# core09e2.net
KiCad netlist of a schematic drawn in EAGLE
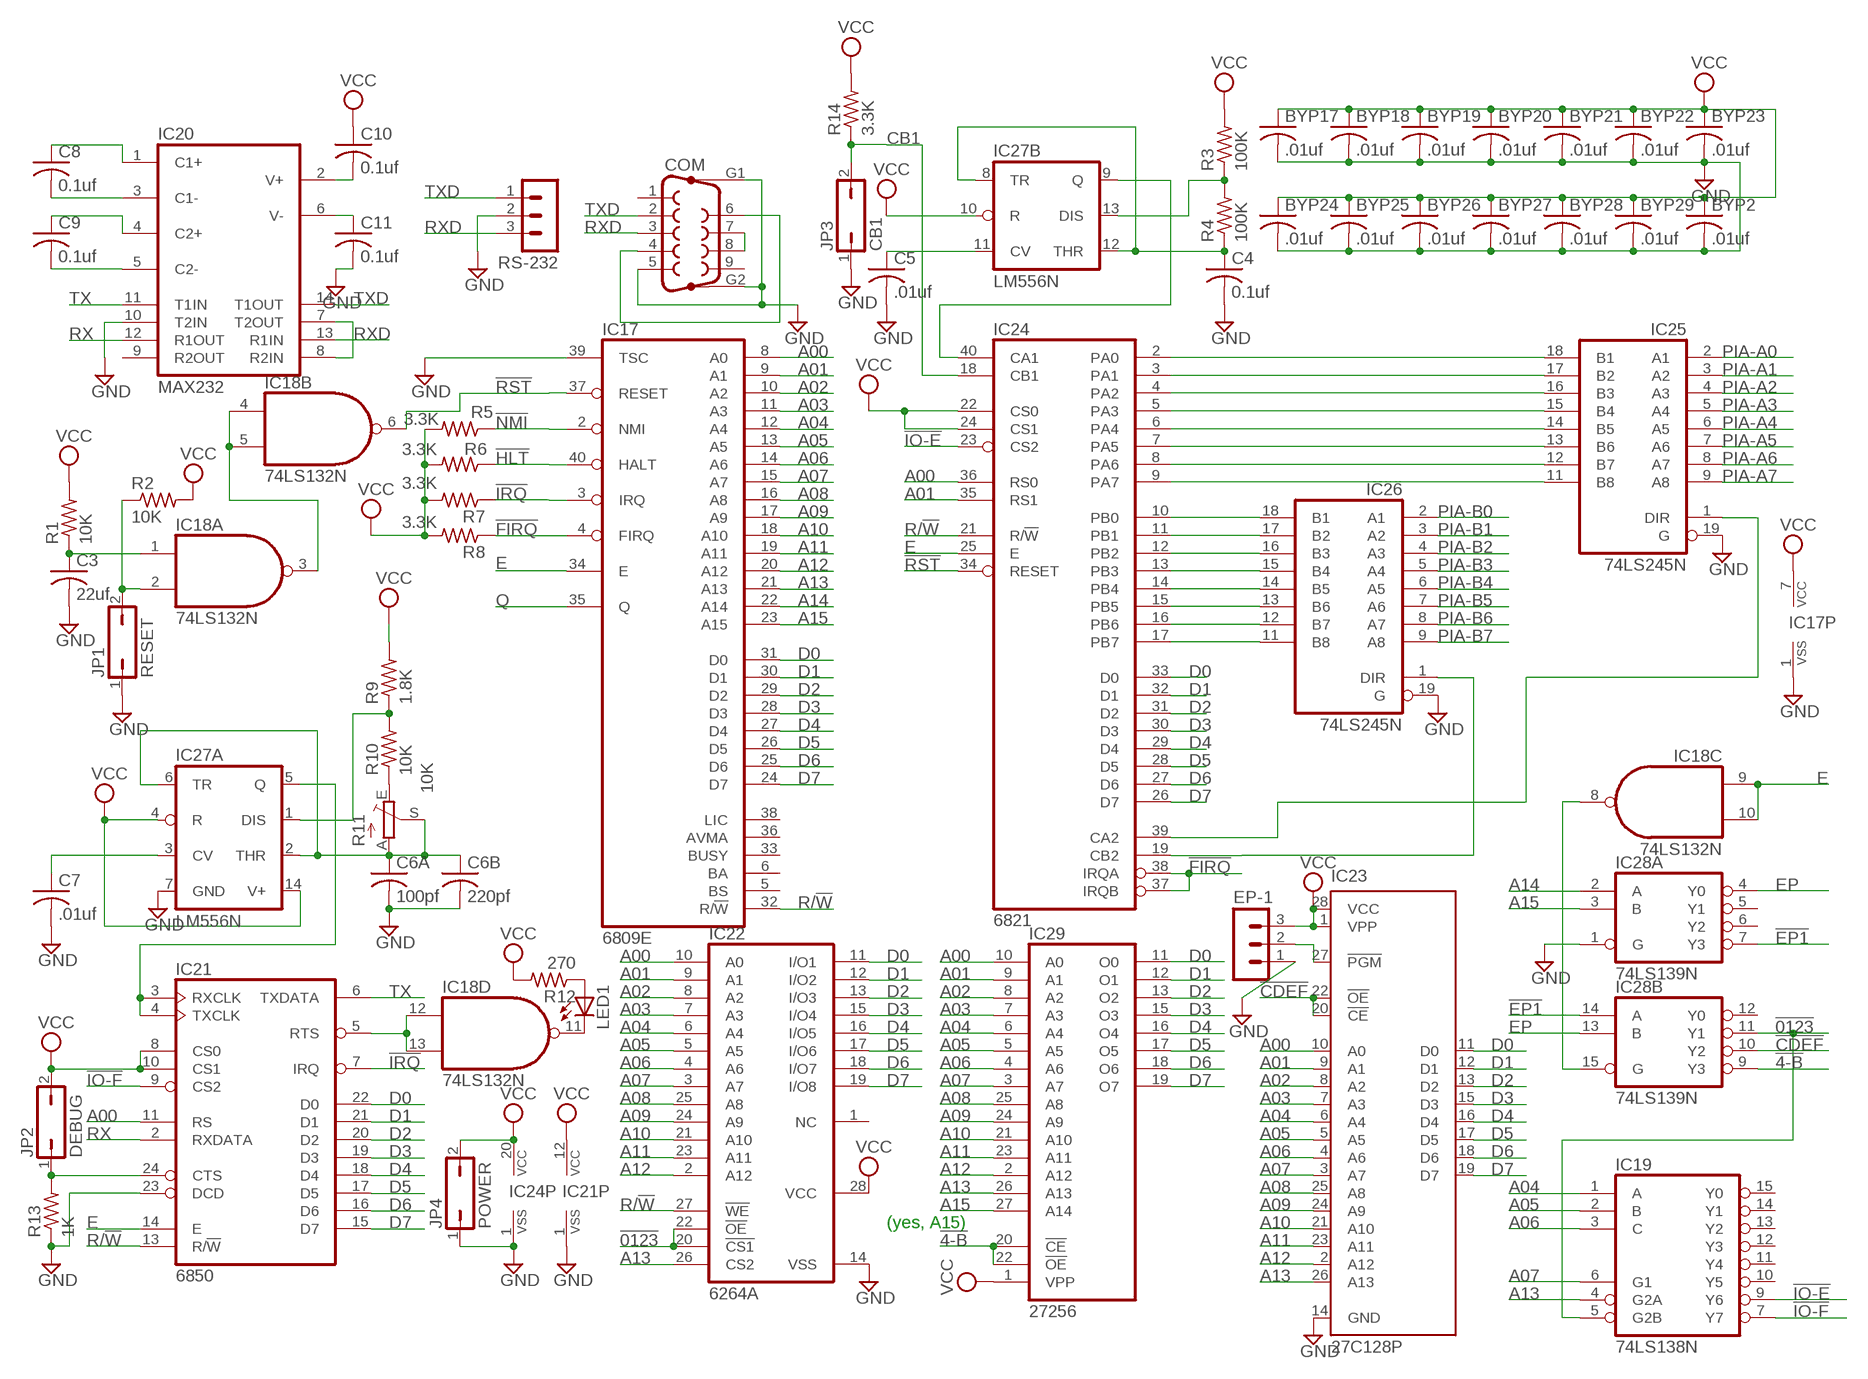
[diagram p0: schematic, sheet 1]
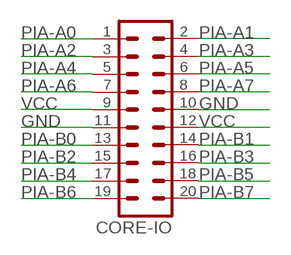
[diagram p1: schematic, sheet 2]
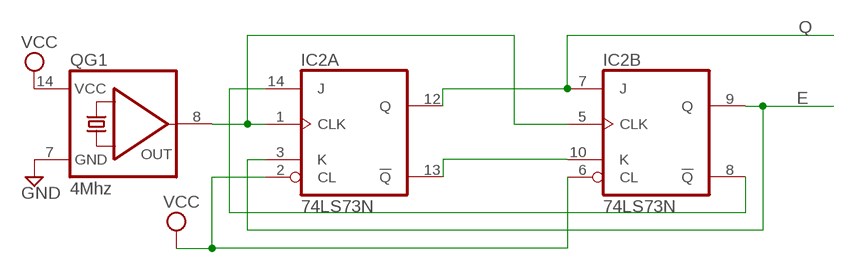
[diagram p2: schematic, sheet 3]

(export (version "E")
  (design (tool "Eeschema 10.0.6"))
  (components
    (comp (ref "BYP2")
      (value ".01uf")
      (footprint "eagle-import:C050-025X075")
      (libsource (lib "eagle-import") (part "C-US050-025X075"))
    )
    (comp (ref "BYP17")
      (value ".01uf")
      (footprint "eagle-import:C050-025X075")
      (libsource (lib "eagle-import") (part "C-US050-025X075"))
    )
    (comp (ref "BYP18")
      (value ".01uf")
      (footprint "eagle-import:C050-025X075")
      (libsource (lib "eagle-import") (part "C-US050-025X075"))
    )
    (comp (ref "BYP19")
      (value ".01uf")
      (footprint "eagle-import:C050-025X075")
      (libsource (lib "eagle-import") (part "C-US050-025X075"))
    )
    (comp (ref "BYP20")
      (value ".01uf")
      (footprint "eagle-import:C050-025X075")
      (libsource (lib "eagle-import") (part "C-US050-025X075"))
    )
    (comp (ref "BYP21")
      (value ".01uf")
      (footprint "eagle-import:C050-025X075")
      (libsource (lib "eagle-import") (part "C-US050-025X075"))
    )
    (comp (ref "BYP22")
      (value ".01uf")
      (footprint "eagle-import:C050-025X075")
      (libsource (lib "eagle-import") (part "C-US050-025X075"))
    )
    (comp (ref "BYP23")
      (value ".01uf")
      (footprint "eagle-import:C050-025X075")
      (libsource (lib "eagle-import") (part "C-US050-025X075"))
    )
    (comp (ref "BYP24")
      (value ".01uf")
      (footprint "eagle-import:C050-025X075")
      (libsource (lib "eagle-import") (part "C-US050-025X075"))
    )
    (comp (ref "BYP25")
      (value ".01uf")
      (footprint "eagle-import:C050-025X075")
      (libsource (lib "eagle-import") (part "C-US050-025X075"))
    )
    (comp (ref "BYP26")
      (value ".01uf")
      (footprint "eagle-import:C050-025X075")
      (libsource (lib "eagle-import") (part "C-US050-025X075"))
    )
    (comp (ref "BYP27")
      (value ".01uf")
      (footprint "eagle-import:C050-025X075")
      (libsource (lib "eagle-import") (part "C-US050-025X075"))
    )
    (comp (ref "BYP28")
      (value ".01uf")
      (footprint "eagle-import:C050-025X075")
      (libsource (lib "eagle-import") (part "C-US050-025X075"))
    )
    (comp (ref "BYP29")
      (value ".01uf")
      (footprint "eagle-import:C050-025X075")
      (libsource (lib "eagle-import") (part "C-US050-025X075"))
    )
    (comp (ref "C3")
      (value "22uf")
      (footprint "eagle-import:C102-054X133")
      (libsource (lib "eagle-import") (part "C-US102-054X133"))
    )
    (comp (ref "C4")
      (value "0.1uf")
      (footprint "eagle-import:C050-025X075")
      (libsource (lib "eagle-import") (part "C-US050-025X075"))
    )
    (comp (ref "C5")
      (value ".01uf")
      (footprint "eagle-import:C050-025X075")
      (libsource (lib "eagle-import") (part "C-US050-025X075"))
    )
    (comp (ref "C6A")
      (value "100pf")
      (footprint "eagle-import:C050-025X075")
      (libsource (lib "eagle-import") (part "C-US050-025X075"))
    )
    (comp (ref "C6B")
      (value "220pf")
      (footprint "eagle-import:C050-025X075")
      (libsource (lib "eagle-import") (part "C-US050-025X075"))
    )
    (comp (ref "C7")
      (value ".01uf")
      (footprint "eagle-import:C050-025X075")
      (libsource (lib "eagle-import") (part "C-US050-025X075"))
    )
    (comp (ref "C8")
      (value "0.1uf")
      (footprint "eagle-import:C050-025X075")
      (libsource (lib "eagle-import") (part "C-US050-025X075"))
    )
    (comp (ref "C9")
      (value "0.1uf")
      (footprint "eagle-import:C050-025X075")
      (libsource (lib "eagle-import") (part "C-US050-025X075"))
    )
    (comp (ref "C10")
      (value "0.1uf")
      (footprint "eagle-import:C050-025X075")
      (libsource (lib "eagle-import") (part "C-US050-025X075"))
    )
    (comp (ref "C11")
      (value "0.1uf")
      (footprint "eagle-import:C050-025X075")
      (libsource (lib "eagle-import") (part "C-US050-025X075"))
    )
    (comp (ref "COM")
      (value "F09HP")
      (footprint "eagle-import:F09HP")
      (libsource (lib "eagle-import") (part "F09HP"))
    )
    (comp (ref "EP-1")
      (value "MA03-1")
      (footprint "eagle-import:MA03-1")
      (libsource (lib "eagle-import") (part "MA03-1"))
    )
    (comp (ref "IC17")
      (value "6809E")
      (footprint "eagle-import:DIL40")
      (fields (field (name "MF") "NTE ELECTRONICS") (field (name "MPN") "NTE6809E"))
      (libsource (lib "eagle-import") (part "6809E"))
    )
    (comp (ref "IC18")
      (value "74LS132N")
      (footprint "eagle-import:DIL14")
      (libsource (lib "eagle-import") (part "7400NLS"))
    )
    (comp (ref "IC19")
      (value "74LS138N")
      (footprint "eagle-import:DIL16")
      (libsource (lib "eagle-import") (part "74138NLS"))
    )
    (comp (ref "IC20")
      (value "MAX232")
      (footprint "eagle-import:DIL16")
      (fields (field (name "MF") "MAXIM") (field (name "MPN") "MAX232ACPE+"))
      (libsource (lib "eagle-import") (part "MAX232"))
    )
    (comp (ref "IC21")
      (value "6850")
      (footprint "eagle-import:DIL24")
      (fields (field (name "MF") "NTE ELECTRONICS") (field (name "MPN") "NTE6850"))
      (libsource (lib "eagle-import") (part "6850"))
    )
    (comp (ref "IC22")
      (value "6264A")
      (footprint "eagle-import:DIL28-6")
      (libsource (lib "eagle-import") (part "6264A"))
    )
    (comp (ref "IC23")
      (value "27C128P")
      (footprint "eagle-import:DIL28-6")
      (libsource (lib "eagle-import") (part "27128PC"))
    )
    (comp (ref "IC24")
      (value "6821")
      (footprint "eagle-import:DIL40")
      (fields (field (name "MF") "NTE ELECTRONICS") (field (name "MPN") "NTE6821"))
      (libsource (lib "eagle-import") (part "6821"))
    )
    (comp (ref "IC25")
      (value "74LS245N")
      (footprint "eagle-import:DIL20")
      (libsource (lib "eagle-import") (part "74245NLS"))
    )
    (comp (ref "IC26")
      (value "74LS245N")
      (footprint "eagle-import:DIL20")
      (libsource (lib "eagle-import") (part "74245NLS"))
    )
    (comp (ref "IC27")
      (value "LM556N")
      (footprint "eagle-import:DIL14")
      (libsource (lib "eagle-import") (part "556NLM"))
    )
    (comp (ref "IC28")
      (value "74LS139N")
      (footprint "eagle-import:DIL16")
      (libsource (lib "eagle-import") (part "74139NLS"))
    )
    (comp (ref "IC29")
      (value "27256")
      (footprint "eagle-import:DIL28")
      (libsource (lib "eagle-import") (part "27256"))
    )
    (comp (ref "JP1")
      (value "RESET")
      (footprint "eagle-import:JP1")
      (libsource (lib "eagle-import") (part "JP1Q"))
    )
    (comp (ref "JP2")
      (value "DEBUG")
      (footprint "eagle-import:JP1")
      (libsource (lib "eagle-import") (part "JP1Q"))
    )
    (comp (ref "JP3")
      (value "CB1")
      (footprint "eagle-import:JP1")
      (libsource (lib "eagle-import") (part "JP1Q"))
    )
    (comp (ref "JP4")
      (value "POWER")
      (footprint "eagle-import:JP1")
      (libsource (lib "eagle-import") (part "JP1Q"))
    )
    (comp (ref "LED1")
      (value "LED3MM")
      (footprint "eagle-import:LED3MM")
      (libsource (lib "eagle-import") (part "LED3MM"))
    )
    (comp (ref "R1")
      (value "10K")
      (footprint "eagle-import:0207_7")
      (libsource (lib "eagle-import") (part "R-US_0207/7"))
    )
    (comp (ref "R2")
      (value "10K")
      (footprint "eagle-import:0207_7")
      (libsource (lib "eagle-import") (part "R-US_0207/7"))
    )
    (comp (ref "R3")
      (value "100K")
      (footprint "eagle-import:0207_7")
      (libsource (lib "eagle-import") (part "R-US_0207/7"))
    )
    (comp (ref "R4")
      (value "100K")
      (footprint "eagle-import:0207_7")
      (libsource (lib "eagle-import") (part "R-US_0207/7"))
    )
    (comp (ref "R5")
      (value "3.3K")
      (footprint "eagle-import:0207_7")
      (libsource (lib "eagle-import") (part "R-US_0207/7"))
    )
    (comp (ref "R6")
      (value "3.3K")
      (footprint "eagle-import:0207_7")
      (libsource (lib "eagle-import") (part "R-US_0207/7"))
    )
    (comp (ref "R7")
      (value "3.3K")
      (footprint "eagle-import:0207_7")
      (libsource (lib "eagle-import") (part "R-US_0207/7"))
    )
    (comp (ref "R8")
      (value "3.3K")
      (footprint "eagle-import:0207_7")
      (libsource (lib "eagle-import") (part "R-US_0207/7"))
    )
    (comp (ref "R9")
      (value "1.8K")
      (footprint "eagle-import:0207_7")
      (libsource (lib "eagle-import") (part "R-US_0207/7"))
    )
    (comp (ref "R10")
      (value "10K")
      (footprint "eagle-import:0207_7")
      (libsource (lib "eagle-import") (part "R-US_0207/7"))
    )
    (comp (ref "R11")
      (value "10K")
      (footprint "eagle-import:SP19L")
      (libsource (lib "eagle-import") (part "TRIM_EU-B90P"))
    )
    (comp (ref "R12")
      (value "270")
      (footprint "eagle-import:0207_7")
      (libsource (lib "eagle-import") (part "R-US_0207/7"))
    )
    (comp (ref "R13")
      (value "1K")
      (footprint "eagle-import:0207_7")
      (libsource (lib "eagle-import") (part "R-US_0207/7"))
    )
    (comp (ref "R14")
      (value "3.3K")
      (footprint "eagle-import:0207_7")
      (libsource (lib "eagle-import") (part "R-US_0207/7"))
    )
    (comp (ref "RS-232")
      (value "MA03-1")
      (footprint "eagle-import:MA03-1")
      (libsource (lib "eagle-import") (part "MA03-1"))
    )
    (comp (ref "IC2")
      (value "74LS73N")
      (footprint "eagle-import:DIL14")
      (libsource (lib "eagle-import") (part "7473NLS"))
    )
    (comp (ref "QG1")
      (value "4Mhz")
      (footprint "eagle-import:DIL14S")
      (libsource (lib "eagle-import") (part "QG5860"))
    )
    (comp (ref "CORE-IO")
      (value "MA10-2")
      (footprint "eagle-import:MA10-2")
      (libsource (lib "eagle-import") (part "MA10-2"))
    )
  )
  (nets
    (net (code "1") (name "A00") (class "Default")
      (node (ref "IC17") (pin "8") (pinfunction "A0_8") (pintype "tri_state"))
      (node (ref "IC21") (pin "11") (pinfunction "RS_11") (pintype "input"))
      (node (ref "IC22") (pin "10") (pinfunction "A0_10") (pintype "input"))
      (node (ref "IC23") (pin "10") (pinfunction "A0_10") (pintype "input"))
      (node (ref "IC24") (pin "36") (pinfunction "RS0_36") (pintype "input"))
      (node (ref "IC29") (pin "10") (pinfunction "A0_10") (pintype "input"))
    )
    (net (code "2") (name "A01") (class "Default")
      (node (ref "IC17") (pin "9") (pinfunction "A1_9") (pintype "tri_state"))
      (node (ref "IC22") (pin "9") (pinfunction "A1_9") (pintype "input"))
      (node (ref "IC23") (pin "9") (pinfunction "A1_9") (pintype "input"))
      (node (ref "IC24") (pin "35") (pinfunction "RS1_35") (pintype "input"))
      (node (ref "IC29") (pin "9") (pinfunction "A1_9") (pintype "input"))
    )
    (net (code "3") (name "A02") (class "Default")
      (node (ref "IC17") (pin "10") (pinfunction "A2_10") (pintype "tri_state"))
      (node (ref "IC22") (pin "8") (pinfunction "A2_8") (pintype "input"))
      (node (ref "IC23") (pin "8") (pinfunction "A2_8") (pintype "input"))
      (node (ref "IC29") (pin "8") (pinfunction "A2_8") (pintype "input"))
    )
    (net (code "4") (name "A03") (class "Default")
      (node (ref "IC17") (pin "11") (pinfunction "A3_11") (pintype "tri_state"))
      (node (ref "IC22") (pin "7") (pinfunction "A3_7") (pintype "input"))
      (node (ref "IC23") (pin "7") (pinfunction "A3_7") (pintype "input"))
      (node (ref "IC29") (pin "7") (pinfunction "A3_7") (pintype "input"))
    )
    (net (code "5") (name "A04") (class "Default")
      (node (ref "IC17") (pin "12") (pinfunction "A4_12") (pintype "tri_state"))
      (node (ref "IC19") (pin "1") (pinfunction "A_1") (pintype "input"))
      (node (ref "IC22") (pin "6") (pinfunction "A4_6") (pintype "input"))
      (node (ref "IC23") (pin "6") (pinfunction "A4_6") (pintype "input"))
      (node (ref "IC29") (pin "6") (pinfunction "A4_6") (pintype "input"))
    )
    (net (code "6") (name "A05") (class "Default")
      (node (ref "IC17") (pin "13") (pinfunction "A5_13") (pintype "tri_state"))
      (node (ref "IC19") (pin "2") (pinfunction "B_2") (pintype "input"))
      (node (ref "IC22") (pin "5") (pinfunction "A5_5") (pintype "input"))
      (node (ref "IC23") (pin "5") (pinfunction "A5_5") (pintype "input"))
      (node (ref "IC29") (pin "5") (pinfunction "A5_5") (pintype "input"))
    )
    (net (code "7") (name "A06") (class "Default")
      (node (ref "IC17") (pin "14") (pinfunction "A6_14") (pintype "tri_state"))
      (node (ref "IC19") (pin "3") (pinfunction "C_3") (pintype "input"))
      (node (ref "IC22") (pin "4") (pinfunction "A6_4") (pintype "input"))
      (node (ref "IC23") (pin "4") (pinfunction "A6_4") (pintype "input"))
      (node (ref "IC29") (pin "4") (pinfunction "A6_4") (pintype "input"))
    )
    (net (code "8") (name "A07") (class "Default")
      (node (ref "IC17") (pin "15") (pinfunction "A7_15") (pintype "tri_state"))
      (node (ref "IC19") (pin "6") (pinfunction "G1_6") (pintype "input"))
      (node (ref "IC22") (pin "3") (pinfunction "A7_3") (pintype "input"))
      (node (ref "IC23") (pin "3") (pinfunction "A7_3") (pintype "input"))
      (node (ref "IC29") (pin "3") (pinfunction "A7_3") (pintype "input"))
    )
    (net (code "9") (name "A08") (class "Default")
      (node (ref "IC17") (pin "16") (pinfunction "A8_16") (pintype "tri_state"))
      (node (ref "IC22") (pin "25") (pinfunction "A8_25") (pintype "input"))
      (node (ref "IC23") (pin "25") (pinfunction "A8_25") (pintype "input"))
      (node (ref "IC29") (pin "25") (pinfunction "A8_25") (pintype "input"))
    )
    (net (code "10") (name "A09") (class "Default")
      (node (ref "IC17") (pin "17") (pinfunction "A9_17") (pintype "tri_state"))
      (node (ref "IC22") (pin "24") (pinfunction "A9_24") (pintype "input"))
      (node (ref "IC23") (pin "24") (pinfunction "A9_24") (pintype "input"))
      (node (ref "IC29") (pin "24") (pinfunction "A9_24") (pintype "input"))
    )
    (net (code "11") (name "A10") (class "Default")
      (node (ref "IC17") (pin "18") (pinfunction "A10_18") (pintype "tri_state"))
      (node (ref "IC22") (pin "21") (pinfunction "A10_21") (pintype "input"))
      (node (ref "IC23") (pin "21") (pinfunction "A10_21") (pintype "input"))
      (node (ref "IC29") (pin "21") (pinfunction "A10_21") (pintype "input"))
    )
    (net (code "12") (name "A11") (class "Default")
      (node (ref "IC17") (pin "19") (pinfunction "A11_19") (pintype "tri_state"))
      (node (ref "IC22") (pin "23") (pinfunction "A11_23") (pintype "input"))
      (node (ref "IC23") (pin "23") (pinfunction "A11_23") (pintype "input"))
      (node (ref "IC29") (pin "23") (pinfunction "A11_23") (pintype "input"))
    )
    (net (code "13") (name "A12") (class "Default")
      (node (ref "IC17") (pin "20") (pinfunction "A12_20") (pintype "tri_state"))
      (node (ref "IC22") (pin "2") (pinfunction "A12_2") (pintype "input"))
      (node (ref "IC23") (pin "2") (pinfunction "A12_2") (pintype "input"))
      (node (ref "IC29") (pin "2") (pinfunction "A12_2") (pintype "input"))
    )
    (net (code "14") (name "A13") (class "Default")
      (node (ref "IC17") (pin "21") (pinfunction "A13_21") (pintype "tri_state"))
      (node (ref "IC19") (pin "4") (pinfunction "G2A_4") (pintype "input"))
      (node (ref "IC22") (pin "26") (pinfunction "CS2_26") (pintype "input"))
      (node (ref "IC23") (pin "26") (pinfunction "A13_26") (pintype "input"))
      (node (ref "IC29") (pin "26") (pinfunction "A13_26") (pintype "input"))
    )
    (net (code "15") (name "A14") (class "Default")
      (node (ref "IC17") (pin "22") (pinfunction "A14_22") (pintype "tri_state"))
      (node (ref "IC28") (pin "2") (pinfunction "A_2") (pintype "input"))
    )
    (net (code "16") (name "A15") (class "Default")
      (node (ref "IC17") (pin "23") (pinfunction "A15_23") (pintype "tri_state"))
      (node (ref "IC28") (pin "3") (pinfunction "B_3") (pintype "input"))
      (node (ref "IC29") (pin "27") (pinfunction "A14_27") (pintype "input"))
    )
    (net (code "17") (name "CB1") (class "Default")
      (node (ref "IC24") (pin "18") (pinfunction "CB1_18") (pintype "input"))
      (node (ref "JP3") (pin "2") (pinfunction "2_2") (pintype "passive"))
      (node (ref "R14") (pin "1") (pinfunction "1_1") (pintype "passive"))
    )
    (net (code "18") (name "D0") (class "Default")
      (node (ref "IC17") (pin "31") (pinfunction "D0_31") (pintype "bidirectional"))
      (node (ref "IC21") (pin "22") (pinfunction "D0_22") (pintype "bidirectional"))
      (node (ref "IC22") (pin "11") (pinfunction "I/O1_11") (pintype "bidirectional"))
      (node (ref "IC23") (pin "11") (pinfunction "D0_11") (pintype "tri_state"))
      (node (ref "IC24") (pin "33") (pinfunction "D0_33") (pintype "bidirectional"))
      (node (ref "IC29") (pin "11") (pinfunction "O0_11") (pintype "tri_state"))
    )
    (net (code "19") (name "D1") (class "Default")
      (node (ref "IC17") (pin "30") (pinfunction "D1_30") (pintype "bidirectional"))
      (node (ref "IC21") (pin "21") (pinfunction "D1_21") (pintype "bidirectional"))
      (node (ref "IC22") (pin "12") (pinfunction "I/O2_12") (pintype "bidirectional"))
      (node (ref "IC23") (pin "12") (pinfunction "D1_12") (pintype "tri_state"))
      (node (ref "IC24") (pin "32") (pinfunction "D1_32") (pintype "bidirectional"))
      (node (ref "IC29") (pin "12") (pinfunction "O1_12") (pintype "tri_state"))
    )
    (net (code "20") (name "D2") (class "Default")
      (node (ref "IC17") (pin "29") (pinfunction "D2_29") (pintype "bidirectional"))
      (node (ref "IC21") (pin "20") (pinfunction "D2_20") (pintype "bidirectional"))
      (node (ref "IC22") (pin "13") (pinfunction "I/O3_13") (pintype "bidirectional"))
      (node (ref "IC23") (pin "13") (pinfunction "D2_13") (pintype "tri_state"))
      (node (ref "IC24") (pin "31") (pinfunction "D2_31") (pintype "bidirectional"))
      (node (ref "IC29") (pin "13") (pinfunction "O2_13") (pintype "tri_state"))
    )
    (net (code "21") (name "D3") (class "Default")
      (node (ref "IC17") (pin "28") (pinfunction "D3_28") (pintype "bidirectional"))
      (node (ref "IC21") (pin "19") (pinfunction "D3_19") (pintype "bidirectional"))
      (node (ref "IC22") (pin "15") (pinfunction "I/O4_15") (pintype "bidirectional"))
      (node (ref "IC23") (pin "15") (pinfunction "D3_15") (pintype "tri_state"))
      (node (ref "IC24") (pin "30") (pinfunction "D3_30") (pintype "bidirectional"))
      (node (ref "IC29") (pin "15") (pinfunction "O3_15") (pintype "tri_state"))
    )
    (net (code "22") (name "D4") (class "Default")
      (node (ref "IC17") (pin "27") (pinfunction "D4_27") (pintype "bidirectional"))
      (node (ref "IC21") (pin "18") (pinfunction "D4_18") (pintype "bidirectional"))
      (node (ref "IC22") (pin "16") (pinfunction "I/O5_16") (pintype "bidirectional"))
      (node (ref "IC23") (pin "16") (pinfunction "D4_16") (pintype "tri_state"))
      (node (ref "IC24") (pin "29") (pinfunction "D4_29") (pintype "bidirectional"))
      (node (ref "IC29") (pin "16") (pinfunction "O4_16") (pintype "tri_state"))
    )
    (net (code "23") (name "D5") (class "Default")
      (node (ref "IC17") (pin "26") (pinfunction "D5_26") (pintype "bidirectional"))
      (node (ref "IC21") (pin "17") (pinfunction "D5_17") (pintype "bidirectional"))
      (node (ref "IC22") (pin "17") (pinfunction "I/O6_17") (pintype "bidirectional"))
      (node (ref "IC23") (pin "17") (pinfunction "D5_17") (pintype "tri_state"))
      (node (ref "IC24") (pin "28") (pinfunction "D5_28") (pintype "bidirectional"))
      (node (ref "IC29") (pin "17") (pinfunction "O5_17") (pintype "tri_state"))
    )
    (net (code "24") (name "D6") (class "Default")
      (node (ref "IC17") (pin "25") (pinfunction "D6_25") (pintype "bidirectional"))
      (node (ref "IC21") (pin "16") (pinfunction "D6_16") (pintype "bidirectional"))
      (node (ref "IC22") (pin "18") (pinfunction "I/O7_18") (pintype "bidirectional"))
      (node (ref "IC23") (pin "18") (pinfunction "D6_18") (pintype "tri_state"))
      (node (ref "IC24") (pin "27") (pinfunction "D6_27") (pintype "bidirectional"))
      (node (ref "IC29") (pin "18") (pinfunction "O6_18") (pintype "tri_state"))
    )
    (net (code "25") (name "D7") (class "Default")
      (node (ref "IC17") (pin "24") (pinfunction "D7_24") (pintype "bidirectional"))
      (node (ref "IC21") (pin "15") (pinfunction "D7_15") (pintype "bidirectional"))
      (node (ref "IC22") (pin "19") (pinfunction "I/O8_19") (pintype "bidirectional"))
      (node (ref "IC23") (pin "19") (pinfunction "D7_19") (pintype "tri_state"))
      (node (ref "IC24") (pin "26") (pinfunction "D7_26") (pintype "bidirectional"))
      (node (ref "IC29") (pin "19") (pinfunction "O7_19") (pintype "tri_state"))
    )
    (net (code "26") (name "E") (class "Default")
      (node (ref "IC17") (pin "34") (pinfunction "E_34") (pintype "input"))
      (node (ref "IC18") (pin "10") (pinfunction "I1_10") (pintype "input"))
      (node (ref "IC18") (pin "9") (pinfunction "I0_9") (pintype "input"))
      (node (ref "IC2") (pin "3") (pinfunction "K_3") (pintype "input"))
      (node (ref "IC2") (pin "9") (pinfunction "Q_9") (pintype "output"))
      (node (ref "IC21") (pin "14") (pinfunction "E_14") (pintype "input"))
      (node (ref "IC24") (pin "25") (pinfunction "E_25") (pintype "input"))
    )
    (net (code "27") (name "EP") (class "Default")
      (node (ref "IC28") (pin "13") (pinfunction "B_13") (pintype "input"))
      (node (ref "IC28") (pin "4") (pinfunction "Y0_4") (pintype "output"))
    )
    (net (code "28") (name "GND") (class "Default")
      (node (ref "BYP17") (pin "2") (pinfunction "2_2") (pintype "passive"))
      (node (ref "BYP18") (pin "2") (pinfunction "2_2") (pintype "passive"))
      (node (ref "BYP19") (pin "2") (pinfunction "2_2") (pintype "passive"))
      (node (ref "BYP2") (pin "2") (pinfunction "2_2") (pintype "passive"))
      (node (ref "BYP20") (pin "2") (pinfunction "2_2") (pintype "passive"))
      (node (ref "BYP21") (pin "2") (pinfunction "2_2") (pintype "passive"))
      (node (ref "BYP22") (pin "2") (pinfunction "2_2") (pintype "passive"))
      (node (ref "BYP23") (pin "2") (pinfunction "2_2") (pintype "passive"))
      (node (ref "BYP24") (pin "2") (pinfunction "2_2") (pintype "passive"))
      (node (ref "BYP25") (pin "2") (pinfunction "2_2") (pintype "passive"))
      (node (ref "BYP26") (pin "2") (pinfunction "2_2") (pintype "passive"))
      (node (ref "BYP27") (pin "2") (pinfunction "2_2") (pintype "passive"))
      (node (ref "BYP28") (pin "2") (pinfunction "2_2") (pintype "passive"))
      (node (ref "BYP29") (pin "2") (pinfunction "2_2") (pintype "passive"))
      (node (ref "C11") (pin "2") (pinfunction "2_2") (pintype "passive"))
      (node (ref "C3") (pin "2") (pinfunction "2_2") (pintype "passive"))
      (node (ref "C4") (pin "2") (pinfunction "2_2") (pintype "passive"))
      (node (ref "C5") (pin "2") (pinfunction "2_2") (pintype "passive"))
      (node (ref "C6A") (pin "2") (pinfunction "2_2") (pintype "passive"))
      (node (ref "C6B") (pin "2") (pinfunction "2_2") (pintype "passive"))
      (node (ref "C7") (pin "2") (pinfunction "2_2") (pintype "passive"))
      (node (ref "COM") (pin "5") (pinfunction "5_5") (pintype "passive"))
      (node (ref "COM") (pin "G1") (pinfunction "G1_G1") (pintype "passive"))
      (node (ref "COM") (pin "G2") (pinfunction "G2_G2") (pintype "passive"))
      (node (ref "CORE-IO") (pin "10") (pinfunction "10_10") (pintype "passive"))
      (node (ref "CORE-IO") (pin "11") (pinfunction "11_11") (pintype "passive"))
      (node (ref "EP-1") (pin "1") (pinfunction "1_1") (pintype "passive"))
      (node (ref "IC17") (pin "1") (pinfunction "VSS_1") (pintype "power_in"))
      (node (ref "IC17") (pin "39") (pinfunction "TSC_39") (pintype "input"))
      (node (ref "IC20") (pin "10") (pinfunction "T2IN_10") (pintype "input"))
      (node (ref "IC21") (pin "1") (pinfunction "VSS_1") (pintype "power_in"))
      (node (ref "IC21") (pin "23") (pinfunction "DCD_23") (pintype "input"))
      (node (ref "IC22") (pin "14") (pinfunction "VSS_14") (pintype "power_in"))
      (node (ref "IC23") (pin "14") (pinfunction "GND_14") (pintype "power_in"))
      (node (ref "IC24") (pin "1") (pinfunction "VSS_1") (pintype "power_in"))
      (node (ref "IC25") (pin "19") (pinfunction "G_19") (pintype "input"))
      (node (ref "IC26") (pin "19") (pinfunction "G_19") (pintype "input"))
      (node (ref "IC27") (pin "7") (pinfunction "GND_7") (pintype "power_in"))
      (node (ref "IC28") (pin "1") (pinfunction "G_1") (pintype "input"))
      (node (ref "JP1") (pin "1") (pinfunction "1_1") (pintype "passive"))
      (node (ref "JP3") (pin "1") (pinfunction "1_1") (pintype "passive"))
      (node (ref "JP4") (pin "1") (pinfunction "1_1") (pintype "passive"))
      (node (ref "QG1") (pin "7") (pinfunction "GND_7") (pintype "power_in"))
      (node (ref "R13") (pin "1") (pinfunction "1_1") (pintype "passive"))
      (node (ref "RS-232") (pin "2") (pinfunction "2_2") (pintype "passive"))
    )
    (net (code "29") (name "Net-(COM-Pad4)") (class "Default")
      (node (ref "COM") (pin "4") (pinfunction "4_4") (pintype "passive"))
      (node (ref "COM") (pin "6") (pinfunction "6_6") (pintype "passive"))
    )
    (net (code "30") (name "Net-(COM-Pad7)") (class "Default")
      (node (ref "COM") (pin "7") (pinfunction "7_7") (pintype "passive"))
      (node (ref "COM") (pin "8") (pinfunction "8_8") (pintype "passive"))
    )
    (net (code "31") (name "Net-(IC2A-CLK)") (class "Default")
      (node (ref "IC2") (pin "1") (pinfunction "CLK_1") (pintype "input"))
      (node (ref "IC2") (pin "5") (pinfunction "CLK_5") (pintype "input"))
      (node (ref "QG1") (pin "8") (pinfunction "OUT_8") (pintype "output"))
    )
    (net (code "32") (name "Net-(IC2A-J)") (class "Default")
      (node (ref "IC2") (pin "14") (pinfunction "J_14") (pintype "input"))
      (node (ref "IC2") (pin "8") (pinfunction "~{Q}_8") (pintype "output"))
    )
    (net (code "33") (name "Net-(IC2A-~{Q})") (class "Default")
      (node (ref "IC2") (pin "10") (pinfunction "K_10") (pintype "input"))
      (node (ref "IC2") (pin "13") (pinfunction "~{Q}_13") (pintype "output"))
    )
    (net (code "34") (name "Net-(IC18A-I0)") (class "Default")
      (node (ref "C3") (pin "1") (pinfunction "1_1") (pintype "passive"))
      (node (ref "IC18") (pin "1") (pinfunction "I0_1") (pintype "input"))
      (node (ref "R1") (pin "1") (pinfunction "1_1") (pintype "passive"))
    )
    (net (code "35") (name "Net-(IC18A-I1)") (class "Default")
      (node (ref "IC18") (pin "2") (pinfunction "I1_2") (pintype "input"))
      (node (ref "JP1") (pin "2") (pinfunction "2_2") (pintype "passive"))
      (node (ref "R2") (pin "1") (pinfunction "1_1") (pintype "passive"))
    )
    (net (code "36") (name "Net-(IC18A-O)") (class "Default")
      (node (ref "IC18") (pin "3") (pinfunction "O_3") (pintype "output"))
      (node (ref "IC18") (pin "4") (pinfunction "I0_4") (pintype "input"))
      (node (ref "IC18") (pin "5") (pinfunction "I1_5") (pintype "input"))
    )
    (net (code "37") (name "Net-(IC18C-O)") (class "Default")
      (node (ref "IC18") (pin "8") (pinfunction "O_8") (pintype "output"))
      (node (ref "IC28") (pin "15") (pinfunction "G_15") (pintype "input"))
    )
    (net (code "38") (name "Net-(IC18D-I0)") (class "Default")
      (node (ref "IC18") (pin "12") (pinfunction "I0_12") (pintype "input"))
      (node (ref "IC18") (pin "13") (pinfunction "I1_13") (pintype "input"))
      (node (ref "IC21") (pin "5") (pinfunction "RTS_5") (pintype "output"))
    )
    (net (code "39") (name "Net-(IC18D-O)") (class "Default")
      (node (ref "IC18") (pin "11") (pinfunction "O_11") (pintype "output"))
      (node (ref "LED1") (pin "K") (pinfunction "C_K") (pintype "passive"))
    )
    (net (code "40") (name "Net-(IC20A-C1+)") (class "Default")
      (node (ref "C8") (pin "1") (pinfunction "1_1") (pintype "passive"))
      (node (ref "IC20") (pin "1") (pinfunction "C1+_1") (pintype "bidirectional"))
    )
    (net (code "41") (name "Net-(IC20A-C1-)") (class "Default")
      (node (ref "C8") (pin "2") (pinfunction "2_2") (pintype "passive"))
      (node (ref "IC20") (pin "3") (pinfunction "C1-_3") (pintype "bidirectional"))
    )
    (net (code "42") (name "Net-(IC20A-C2+)") (class "Default")
      (node (ref "C9") (pin "1") (pinfunction "1_1") (pintype "passive"))
      (node (ref "IC20") (pin "4") (pinfunction "C2+_4") (pintype "bidirectional"))
    )
    (net (code "43") (name "Net-(IC20A-C2-)") (class "Default")
      (node (ref "C9") (pin "2") (pinfunction "2_2") (pintype "passive"))
      (node (ref "IC20") (pin "5") (pinfunction "C2-_5") (pintype "bidirectional"))
    )
    (net (code "44") (name "Net-(IC20A-R2IN)") (class "Default")
      (node (ref "IC20") (pin "7") (pinfunction "T2OUT_7") (pintype "output"))
      (node (ref "IC20") (pin "8") (pinfunction "R2IN_8") (pintype "input"))
    )
    (net (code "45") (name "Net-(IC20A-V+)") (class "Default")
      (node (ref "C10") (pin "2") (pinfunction "2_2") (pintype "passive"))
      (node (ref "IC20") (pin "2") (pinfunction "V+_2") (pintype "bidirectional"))
    )
    (net (code "46") (name "Net-(IC20A-V-)") (class "Default")
      (node (ref "C11") (pin "1") (pinfunction "1_1") (pintype "passive"))
      (node (ref "IC20") (pin "6") (pinfunction "V-_6") (pintype "bidirectional"))
    )
    (net (code "47") (name "Net-(IC21A-CTS)") (class "Default")
      (node (ref "IC21") (pin "24") (pinfunction "CTS_24") (pintype "input"))
      (node (ref "JP2") (pin "1") (pinfunction "1_1") (pintype "passive"))
      (node (ref "R13") (pin "2") (pinfunction "2_2") (pintype "passive"))
    )
    (net (code "48") (name "Net-(IC21A-RXCLK)") (class "Default")
      (node (ref "IC21") (pin "3") (pinfunction "RXCLK_3") (pintype "input"))
      (node (ref "IC21") (pin "4") (pinfunction "TXCLK_4") (pintype "input"))
      (node (ref "IC27") (pin "5") (pinfunction "Q_5") (pintype "output"))
    )
    (net (code "49") (name "Net-(IC23-~{PGM})") (class "Default")
      (node (ref "EP-1") (pin "2") (pinfunction "2_2") (pintype "passive"))
      (node (ref "IC23") (pin "27") (pinfunction "~{PGM}_27") (pintype "passive"))
    )
    (net (code "50") (name "Net-(IC24A-CA1)") (class "Default")
      (node (ref "IC24") (pin "40") (pinfunction "CA1_40") (pintype "input"))
      (node (ref "IC27") (pin "9") (pinfunction "Q_9") (pintype "output"))
    )
    (net (code "51") (name "Net-(IC24A-CA2)") (class "Default")
      (node (ref "IC24") (pin "39") (pinfunction "CA2_39") (pintype "bidirectional"))
      (node (ref "IC25") (pin "1") (pinfunction "DIR_1") (pintype "input"))
    )
    (net (code "52") (name "Net-(IC24A-CB2)") (class "Default")
      (node (ref "IC24") (pin "19") (pinfunction "CB2_19") (pintype "bidirectional"))
      (node (ref "IC26") (pin "1") (pinfunction "DIR_1") (pintype "input"))
    )
    (net (code "53") (name "Net-(IC24A-PA0)") (class "Default")
      (node (ref "IC24") (pin "2") (pinfunction "PA0_2") (pintype "bidirectional"))
      (node (ref "IC25") (pin "18") (pinfunction "B1_18") (pintype "bidirectional"))
    )
    (net (code "54") (name "Net-(IC24A-PA1)") (class "Default")
      (node (ref "IC24") (pin "3") (pinfunction "PA1_3") (pintype "bidirectional"))
      (node (ref "IC25") (pin "17") (pinfunction "B2_17") (pintype "bidirectional"))
    )
    (net (code "55") (name "Net-(IC24A-PA2)") (class "Default")
      (node (ref "IC24") (pin "4") (pinfunction "PA2_4") (pintype "bidirectional"))
      (node (ref "IC25") (pin "16") (pinfunction "B3_16") (pintype "bidirectional"))
    )
    (net (code "56") (name "Net-(IC24A-PA3)") (class "Default")
      (node (ref "IC24") (pin "5") (pinfunction "PA3_5") (pintype "bidirectional"))
      (node (ref "IC25") (pin "15") (pinfunction "B4_15") (pintype "bidirectional"))
    )
    (net (code "57") (name "Net-(IC24A-PA4)") (class "Default")
      (node (ref "IC24") (pin "6") (pinfunction "PA4_6") (pintype "bidirectional"))
      (node (ref "IC25") (pin "14") (pinfunction "B5_14") (pintype "bidirectional"))
    )
    (net (code "58") (name "Net-(IC24A-PA5)") (class "Default")
      (node (ref "IC24") (pin "7") (pinfunction "PA5_7") (pintype "bidirectional"))
      (node (ref "IC25") (pin "13") (pinfunction "B6_13") (pintype "bidirectional"))
    )
    (net (code "59") (name "Net-(IC24A-PA6)") (class "Default")
      (node (ref "IC24") (pin "8") (pinfunction "PA6_8") (pintype "bidirectional"))
      (node (ref "IC25") (pin "12") (pinfunction "B7_12") (pintype "bidirectional"))
    )
    (net (code "60") (name "Net-(IC24A-PA7)") (class "Default")
      (node (ref "IC24") (pin "9") (pinfunction "PA7_9") (pintype "bidirectional"))
      (node (ref "IC25") (pin "11") (pinfunction "B8_11") (pintype "bidirectional"))
    )
    (net (code "61") (name "Net-(IC24A-PB0)") (class "Default")
      (node (ref "IC24") (pin "10") (pinfunction "PB0_10") (pintype "bidirectional"))
      (node (ref "IC26") (pin "18") (pinfunction "B1_18") (pintype "bidirectional"))
    )
    (net (code "62") (name "Net-(IC24A-PB1)") (class "Default")
      (node (ref "IC24") (pin "11") (pinfunction "PB1_11") (pintype "bidirectional"))
      (node (ref "IC26") (pin "17") (pinfunction "B2_17") (pintype "bidirectional"))
    )
    (net (code "63") (name "Net-(IC24A-PB2)") (class "Default")
      (node (ref "IC24") (pin "12") (pinfunction "PB2_12") (pintype "bidirectional"))
      (node (ref "IC26") (pin "16") (pinfunction "B3_16") (pintype "bidirectional"))
    )
    (net (code "64") (name "Net-(IC24A-PB3)") (class "Default")
      (node (ref "IC24") (pin "13") (pinfunction "PB3_13") (pintype "bidirectional"))
      (node (ref "IC26") (pin "15") (pinfunction "B4_15") (pintype "bidirectional"))
    )
    (net (code "65") (name "Net-(IC24A-PB4)") (class "Default")
      (node (ref "IC24") (pin "14") (pinfunction "PB4_14") (pintype "bidirectional"))
      (node (ref "IC26") (pin "14") (pinfunction "B5_14") (pintype "bidirectional"))
    )
    (net (code "66") (name "Net-(IC24A-PB5)") (class "Default")
      (node (ref "IC24") (pin "15") (pinfunction "PB5_15") (pintype "bidirectional"))
      (node (ref "IC26") (pin "13") (pinfunction "B6_13") (pintype "bidirectional"))
    )
    (net (code "67") (name "Net-(IC24A-PB6)") (class "Default")
      (node (ref "IC24") (pin "16") (pinfunction "PB6_16") (pintype "bidirectional"))
      (node (ref "IC26") (pin "12") (pinfunction "B7_12") (pintype "bidirectional"))
    )
    (net (code "68") (name "Net-(IC24A-PB7)") (class "Default")
      (node (ref "IC24") (pin "17") (pinfunction "PB7_17") (pintype "bidirectional"))
      (node (ref "IC26") (pin "11") (pinfunction "B8_11") (pintype "bidirectional"))
    )
    (net (code "69") (name "Net-(IC27A-CV)") (class "Default")
      (node (ref "C7") (pin "1") (pinfunction "1_1") (pintype "passive"))
      (node (ref "IC27") (pin "3") (pinfunction "CV_3") (pintype "input"))
    )
    (net (code "70") (name "Net-(IC27A-DIS)") (class "Default")
      (node (ref "IC27") (pin "1") (pinfunction "DIS_1") (pintype "input"))
      (node (ref "R10") (pin "2") (pinfunction "2_2") (pintype "passive"))
      (node (ref "R9") (pin "1") (pinfunction "1_1") (pintype "passive"))
    )
    (net (code "71") (name "Net-(IC27A-THR)") (class "Default")
      (node (ref "C6A") (pin "1") (pinfunction "1_1") (pintype "passive"))
      (node (ref "C6B") (pin "1") (pinfunction "1_1") (pintype "passive"))
      (node (ref "IC27") (pin "2") (pinfunction "THR_2") (pintype "input"))
      (node (ref "IC27") (pin "6") (pinfunction "TR_6") (pintype "input"))
      (node (ref "R11") (pin "A") (pinfunction "A_A") (pintype "passive"))
      (node (ref "R11") (pin "S") (pinfunction "S_S") (pintype "passive"))
    )
    (net (code "72") (name "Net-(IC27B-CV)") (class "Default")
      (node (ref "C5") (pin "1") (pinfunction "1_1") (pintype "passive"))
      (node (ref "IC27") (pin "11") (pinfunction "CV_11") (pintype "input"))
    )
    (net (code "73") (name "Net-(IC27B-DIS)") (class "Default")
      (node (ref "IC27") (pin "13") (pinfunction "DIS_13") (pintype "input"))
      (node (ref "R3") (pin "1") (pinfunction "1_1") (pintype "passive"))
      (node (ref "R4") (pin "2") (pinfunction "2_2") (pintype "passive"))
    )
    (net (code "74") (name "Net-(IC27B-THR)") (class "Default")
      (node (ref "C4") (pin "1") (pinfunction "1_1") (pintype "passive"))
      (node (ref "IC27") (pin "12") (pinfunction "THR_12") (pintype "input"))
      (node (ref "IC27") (pin "8") (pinfunction "TR_8") (pintype "input"))
      (node (ref "R4") (pin "1") (pinfunction "1_1") (pintype "passive"))
    )
    (net (code "75") (name "Net-(LED1-PadA)") (class "Default")
      (node (ref "LED1") (pin "A") (pinfunction "A_A") (pintype "passive"))
      (node (ref "R12") (pin "1") (pinfunction "1_1") (pintype "passive"))
    )
    (net (code "76") (name "Net-(R10-Pad1)") (class "Default")
      (node (ref "R10") (pin "1") (pinfunction "1_1") (pintype "passive"))
      (node (ref "R11") (pin "E") (pinfunction "E_E") (pintype "passive"))
    )
    (net (code "77") (name "PIA-A0") (class "Default")
      (node (ref "CORE-IO") (pin "1") (pinfunction "1_1") (pintype "passive"))
      (node (ref "IC25") (pin "2") (pinfunction "A1_2") (pintype "bidirectional"))
    )
    (net (code "78") (name "PIA-A1") (class "Default")
      (node (ref "CORE-IO") (pin "2") (pinfunction "2_2") (pintype "passive"))
      (node (ref "IC25") (pin "3") (pinfunction "A2_3") (pintype "bidirectional"))
    )
    (net (code "79") (name "PIA-A2") (class "Default")
      (node (ref "CORE-IO") (pin "3") (pinfunction "3_3") (pintype "passive"))
      (node (ref "IC25") (pin "4") (pinfunction "A3_4") (pintype "bidirectional"))
    )
    (net (code "80") (name "PIA-A3") (class "Default")
      (node (ref "CORE-IO") (pin "4") (pinfunction "4_4") (pintype "passive"))
      (node (ref "IC25") (pin "5") (pinfunction "A4_5") (pintype "bidirectional"))
    )
    (net (code "81") (name "PIA-A4") (class "Default")
      (node (ref "CORE-IO") (pin "5") (pinfunction "5_5") (pintype "passive"))
      (node (ref "IC25") (pin "6") (pinfunction "A5_6") (pintype "bidirectional"))
    )
    (net (code "82") (name "PIA-A5") (class "Default")
      (node (ref "CORE-IO") (pin "6") (pinfunction "6_6") (pintype "passive"))
      (node (ref "IC25") (pin "7") (pinfunction "A6_7") (pintype "bidirectional"))
    )
    (net (code "83") (name "PIA-A6") (class "Default")
      (node (ref "CORE-IO") (pin "7") (pinfunction "7_7") (pintype "passive"))
      (node (ref "IC25") (pin "8") (pinfunction "A7_8") (pintype "bidirectional"))
    )
    (net (code "84") (name "PIA-A7") (class "Default")
      (node (ref "CORE-IO") (pin "8") (pinfunction "8_8") (pintype "passive"))
      (node (ref "IC25") (pin "9") (pinfunction "A8_9") (pintype "bidirectional"))
    )
    (net (code "85") (name "PIA-B0") (class "Default")
      (node (ref "CORE-IO") (pin "13") (pinfunction "13_13") (pintype "passive"))
      (node (ref "IC26") (pin "2") (pinfunction "A1_2") (pintype "bidirectional"))
    )
    (net (code "86") (name "PIA-B1") (class "Default")
      (node (ref "CORE-IO") (pin "14") (pinfunction "14_14") (pintype "passive"))
      (node (ref "IC26") (pin "3") (pinfunction "A2_3") (pintype "bidirectional"))
    )
    (net (code "87") (name "PIA-B2") (class "Default")
      (node (ref "CORE-IO") (pin "15") (pinfunction "15_15") (pintype "passive"))
      (node (ref "IC26") (pin "4") (pinfunction "A3_4") (pintype "bidirectional"))
    )
    (net (code "88") (name "PIA-B3") (class "Default")
      (node (ref "CORE-IO") (pin "16") (pinfunction "16_16") (pintype "passive"))
      (node (ref "IC26") (pin "5") (pinfunction "A4_5") (pintype "bidirectional"))
    )
    (net (code "89") (name "PIA-B4") (class "Default")
      (node (ref "CORE-IO") (pin "17") (pinfunction "17_17") (pintype "passive"))
      (node (ref "IC26") (pin "6") (pinfunction "A5_6") (pintype "bidirectional"))
    )
    (net (code "90") (name "PIA-B5") (class "Default")
      (node (ref "CORE-IO") (pin "18") (pinfunction "18_18") (pintype "passive"))
      (node (ref "IC26") (pin "7") (pinfunction "A6_7") (pintype "bidirectional"))
    )
    (net (code "91") (name "PIA-B6") (class "Default")
      (node (ref "CORE-IO") (pin "19") (pinfunction "19_19") (pintype "passive"))
      (node (ref "IC26") (pin "8") (pinfunction "A7_8") (pintype "bidirectional"))
    )
    (net (code "92") (name "PIA-B7") (class "Default")
      (node (ref "CORE-IO") (pin "20") (pinfunction "20_20") (pintype "passive"))
      (node (ref "IC26") (pin "9") (pinfunction "A8_9") (pintype "bidirectional"))
    )
    (net (code "93") (name "Q") (class "Default")
      (node (ref "IC17") (pin "35") (pinfunction "Q_35") (pintype "input"))
      (node (ref "IC2") (pin "12") (pinfunction "Q_12") (pintype "output"))
      (node (ref "IC2") (pin "7") (pinfunction "J_7") (pintype "input"))
    )
    (net (code "94") (name "RX") (class "Default")
      (node (ref "IC20") (pin "12") (pinfunction "R1OUT_12") (pintype "output"))
      (node (ref "IC21") (pin "2") (pinfunction "RXDATA_2") (pintype "input"))
    )
    (net (code "95") (name "RXD") (class "Default")
      (node (ref "COM") (pin "3") (pinfunction "3_3") (pintype "passive"))
      (node (ref "IC20") (pin "13") (pinfunction "R1IN_13") (pintype "input"))
      (node (ref "RS-232") (pin "3") (pinfunction "3_3") (pintype "passive"))
    )
    (net (code "96") (name "R{slash}~{W}") (class "Default")
      (node (ref "IC17") (pin "32") (pinfunction "R/~{W}_32") (pintype "output"))
      (node (ref "IC21") (pin "13") (pinfunction "R/~{W}_13") (pintype "input"))
      (node (ref "IC22") (pin "27") (pinfunction "~{WE}_27") (pintype "input"))
      (node (ref "IC24") (pin "21") (pinfunction "R/~{W}_21") (pintype "input"))
    )
    (net (code "97") (name "TX") (class "Default")
      (node (ref "IC20") (pin "11") (pinfunction "T1IN_11") (pintype "input"))
      (node (ref "IC21") (pin "6") (pinfunction "TXDATA_6") (pintype "output"))
    )
    (net (code "98") (name "TXD") (class "Default")
      (node (ref "COM") (pin "2") (pinfunction "2_2") (pintype "passive"))
      (node (ref "IC20") (pin "14") (pinfunction "T1OUT_14") (pintype "output"))
      (node (ref "RS-232") (pin "1") (pinfunction "1_1") (pintype "passive"))
    )
    (net (code "99") (name "VCC") (class "Default")
      (node (ref "BYP17") (pin "1") (pinfunction "1_1") (pintype "passive"))
      (node (ref "BYP18") (pin "1") (pinfunction "1_1") (pintype "passive"))
      (node (ref "BYP19") (pin "1") (pinfunction "1_1") (pintype "passive"))
      (node (ref "BYP2") (pin "1") (pinfunction "1_1") (pintype "passive"))
      (node (ref "BYP20") (pin "1") (pinfunction "1_1") (pintype "passive"))
      (node (ref "BYP21") (pin "1") (pinfunction "1_1") (pintype "passive"))
      (node (ref "BYP22") (pin "1") (pinfunction "1_1") (pintype "passive"))
      (node (ref "BYP23") (pin "1") (pinfunction "1_1") (pintype "passive"))
      (node (ref "BYP24") (pin "1") (pinfunction "1_1") (pintype "passive"))
      (node (ref "BYP25") (pin "1") (pinfunction "1_1") (pintype "passive"))
      (node (ref "BYP26") (pin "1") (pinfunction "1_1") (pintype "passive"))
      (node (ref "BYP27") (pin "1") (pinfunction "1_1") (pintype "passive"))
      (node (ref "BYP28") (pin "1") (pinfunction "1_1") (pintype "passive"))
      (node (ref "BYP29") (pin "1") (pinfunction "1_1") (pintype "passive"))
      (node (ref "C10") (pin "1") (pinfunction "1_1") (pintype "passive"))
      (node (ref "CORE-IO") (pin "12") (pinfunction "12_12") (pintype "passive"))
      (node (ref "CORE-IO") (pin "9") (pinfunction "9_9") (pintype "passive"))
      (node (ref "EP-1") (pin "3") (pinfunction "3_3") (pintype "passive"))
      (node (ref "IC17") (pin "7") (pinfunction "VCC_7") (pintype "power_in"))
      (node (ref "IC2") (pin "2") (pinfunction "CL_2") (pintype "input"))
      (node (ref "IC2") (pin "6") (pinfunction "CL_6") (pintype "input"))
      (node (ref "IC21") (pin "10") (pinfunction "CS1_10") (pintype "input"))
      (node (ref "IC21") (pin "12") (pinfunction "VCC_12") (pintype "power_in"))
      (node (ref "IC21") (pin "8") (pinfunction "CS0_8") (pintype "input"))
      (node (ref "IC22") (pin "28") (pinfunction "VCC_28") (pintype "power_in"))
      (node (ref "IC23") (pin "1") (pinfunction "VPP_1") (pintype "input"))
      (node (ref "IC23") (pin "28") (pinfunction "VCC_28") (pintype "power_in"))
      (node (ref "IC24") (pin "20") (pinfunction "VCC_20") (pintype "power_in"))
      (node (ref "IC24") (pin "22") (pinfunction "CS0_22") (pintype "input"))
      (node (ref "IC24") (pin "24") (pinfunction "CS1_24") (pintype "input"))
      (node (ref "IC27") (pin "10") (pinfunction "R_10") (pintype "input"))
      (node (ref "IC27") (pin "14") (pinfunction "V+_14") (pintype "power_in"))
      (node (ref "IC27") (pin "4") (pinfunction "R_4") (pintype "input"))
      (node (ref "IC29") (pin "1") (pinfunction "VPP_1") (pintype "input"))
      (node (ref "JP2") (pin "2") (pinfunction "2_2") (pintype "passive"))
      (node (ref "JP4") (pin "2") (pinfunction "2_2") (pintype "passive"))
      (node (ref "QG1") (pin "14") (pinfunction "VCC_14") (pintype "power_in"))
      (node (ref "R1") (pin "2") (pinfunction "2_2") (pintype "passive"))
      (node (ref "R12") (pin "2") (pinfunction "2_2") (pintype "passive"))
      (node (ref "R14") (pin "2") (pinfunction "2_2") (pintype "passive"))
      (node (ref "R2") (pin "2") (pinfunction "2_2") (pintype "passive"))
      (node (ref "R3") (pin "2") (pinfunction "2_2") (pintype "passive"))
      (node (ref "R5") (pin "2") (pinfunction "2_2") (pintype "passive"))
      (node (ref "R6") (pin "2") (pinfunction "2_2") (pintype "passive"))
      (node (ref "R7") (pin "2") (pinfunction "2_2") (pintype "passive"))
      (node (ref "R8") (pin "2") (pinfunction "2_2") (pintype "passive"))
      (node (ref "R9") (pin "2") (pinfunction "2_2") (pintype "passive"))
    )
    (net (code "100") (name "unconnected-(COM-Pad1)") (class "Default")
      (node (ref "COM") (pin "1") (pinfunction "1_1") (pintype "passive"))
    )
    (net (code "101") (name "unconnected-(COM-Pad9)") (class "Default")
      (node (ref "COM") (pin "9") (pinfunction "9_9") (pintype "passive"))
    )
    (net (code "102") (name "unconnected-(IC17A-AVMA-Pad36)") (class "Default")
      (node (ref "IC17") (pin "36") (pinfunction "AVMA_36") (pintype "output"))
    )
    (net (code "103") (name "unconnected-(IC17A-BA-Pad6)") (class "Default")
      (node (ref "IC17") (pin "6") (pinfunction "BA_6") (pintype "output"))
    )
    (net (code "104") (name "unconnected-(IC17A-BS-Pad5)") (class "Default")
      (node (ref "IC17") (pin "5") (pinfunction "BS_5") (pintype "output"))
    )
    (net (code "105") (name "unconnected-(IC17A-BUSY-Pad33)") (class "Default")
      (node (ref "IC17") (pin "33") (pinfunction "BUSY_33") (pintype "output"))
    )
    (net (code "106") (name "unconnected-(IC17A-LIC-Pad38)") (class "Default")
      (node (ref "IC17") (pin "38") (pinfunction "LIC_38") (pintype "output"))
    )
    (net (code "107") (name "unconnected-(IC19A-Y0-Pad15)") (class "Default")
      (node (ref "IC19") (pin "15") (pinfunction "Y0_15") (pintype "output"))
    )
    (net (code "108") (name "unconnected-(IC19A-Y1-Pad14)") (class "Default")
      (node (ref "IC19") (pin "14") (pinfunction "Y1_14") (pintype "output"))
    )
    (net (code "109") (name "unconnected-(IC19A-Y2-Pad13)") (class "Default")
      (node (ref "IC19") (pin "13") (pinfunction "Y2_13") (pintype "output"))
    )
    (net (code "110") (name "unconnected-(IC19A-Y3-Pad12)") (class "Default")
      (node (ref "IC19") (pin "12") (pinfunction "Y3_12") (pintype "output"))
    )
    (net (code "111") (name "unconnected-(IC19A-Y4-Pad11)") (class "Default")
      (node (ref "IC19") (pin "11") (pinfunction "Y4_11") (pintype "output"))
    )
    (net (code "112") (name "unconnected-(IC19A-Y5-Pad10)") (class "Default")
      (node (ref "IC19") (pin "10") (pinfunction "Y5_10") (pintype "output"))
    )
    (net (code "113") (name "unconnected-(IC20A-R2OUT-Pad9)") (class "Default")
      (node (ref "IC20") (pin "9") (pinfunction "R2OUT_9") (pintype "output"))
    )
    (net (code "114") (name "unconnected-(IC22-NC-Pad1)") (class "Default")
      (node (ref "IC22") (pin "1") (pinfunction "NC_1") (pintype "no_connect"))
    )
    (net (code "115") (name "unconnected-(IC28A-Y1-Pad5)") (class "Default")
      (node (ref "IC28") (pin "5") (pinfunction "Y1_5") (pintype "output"))
    )
    (net (code "116") (name "unconnected-(IC28A-Y2-Pad6)") (class "Default")
      (node (ref "IC28") (pin "6") (pinfunction "Y2_6") (pintype "output"))
    )
    (net (code "117") (name "unconnected-(IC28B-Y0-Pad12)") (class "Default")
      (node (ref "IC28") (pin "12") (pinfunction "Y0_12") (pintype "output"))
    )
    (net (code "118") (name "~{4-B}") (class "Default")
      (node (ref "IC28") (pin "9") (pinfunction "Y3_9") (pintype "output"))
      (node (ref "IC29") (pin "20") (pinfunction "~{CE}_20") (pintype "input"))
      (node (ref "IC29") (pin "22") (pinfunction "~{OE}_22") (pintype "input"))
    )
    (net (code "119") (name "~{0123}") (class "Default")
      (node (ref "IC19") (pin "5") (pinfunction "G2B_5") (pintype "input"))
      (node (ref "IC22") (pin "20") (pinfunction "~{CS1}_20") (pintype "input"))
      (node (ref "IC22") (pin "22") (pinfunction "~{OE}_22") (pintype "input"))
      (node (ref "IC28") (pin "11") (pinfunction "Y1_11") (pintype "output"))
    )
    (net (code "120") (name "~{CDEF}") (class "Default")
      (node (ref "IC23") (pin "20") (pinfunction "~{CE}_20") (pintype "input"))
      (node (ref "IC23") (pin "22") (pinfunction "~{OE}_22") (pintype "input"))
      (node (ref "IC28") (pin "10") (pinfunction "Y2_10") (pintype "output"))
    )
    (net (code "121") (name "~{EP1}") (class "Default")
      (node (ref "IC28") (pin "14") (pinfunction "A_14") (pintype "input"))
      (node (ref "IC28") (pin "7") (pinfunction "Y3_7") (pintype "output"))
    )
    (net (code "122") (name "~{FIRQ}") (class "Default")
      (node (ref "IC17") (pin "4") (pinfunction "FIRQ_4") (pintype "input"))
      (node (ref "IC24") (pin "37") (pinfunction "IRQB_37") (pintype "open_collector"))
      (node (ref "IC24") (pin "38") (pinfunction "IRQA_38") (pintype "open_collector"))
      (node (ref "R8") (pin "1") (pinfunction "1_1") (pintype "passive"))
    )
    (net (code "123") (name "~{HLT}") (class "Default")
      (node (ref "IC17") (pin "40") (pinfunction "HALT_40") (pintype "input"))
      (node (ref "R5") (pin "1") (pinfunction "1_1") (pintype "passive"))
    )
    (net (code "124") (name "~{IO-E}") (class "Default")
      (node (ref "IC19") (pin "9") (pinfunction "Y6_9") (pintype "output"))
      (node (ref "IC24") (pin "23") (pinfunction "CS2_23") (pintype "input"))
    )
    (net (code "125") (name "~{IO-F}") (class "Default")
      (node (ref "IC19") (pin "7") (pinfunction "Y7_7") (pintype "output"))
      (node (ref "IC21") (pin "9") (pinfunction "CS2_9") (pintype "input"))
    )
    (net (code "126") (name "~{IRQ}") (class "Default")
      (node (ref "IC17") (pin "3") (pinfunction "IRQ_3") (pintype "input"))
      (node (ref "IC21") (pin "7") (pinfunction "IRQ_7") (pintype "output"))
      (node (ref "R7") (pin "1") (pinfunction "1_1") (pintype "passive"))
    )
    (net (code "127") (name "~{NMI}") (class "Default")
      (node (ref "IC17") (pin "2") (pinfunction "NMI_2") (pintype "input"))
      (node (ref "R6") (pin "1") (pinfunction "1_1") (pintype "passive"))
    )
    (net (code "128") (name "~{RST}") (class "Default")
      (node (ref "IC17") (pin "37") (pinfunction "RESET_37") (pintype "input"))
      (node (ref "IC18") (pin "6") (pinfunction "O_6") (pintype "output"))
      (node (ref "IC24") (pin "34") (pinfunction "RESET_34") (pintype "input"))
    )
  )
)
